# diff_probe_top.net
KiCad netlist of a schematic drawn in Altium Designer
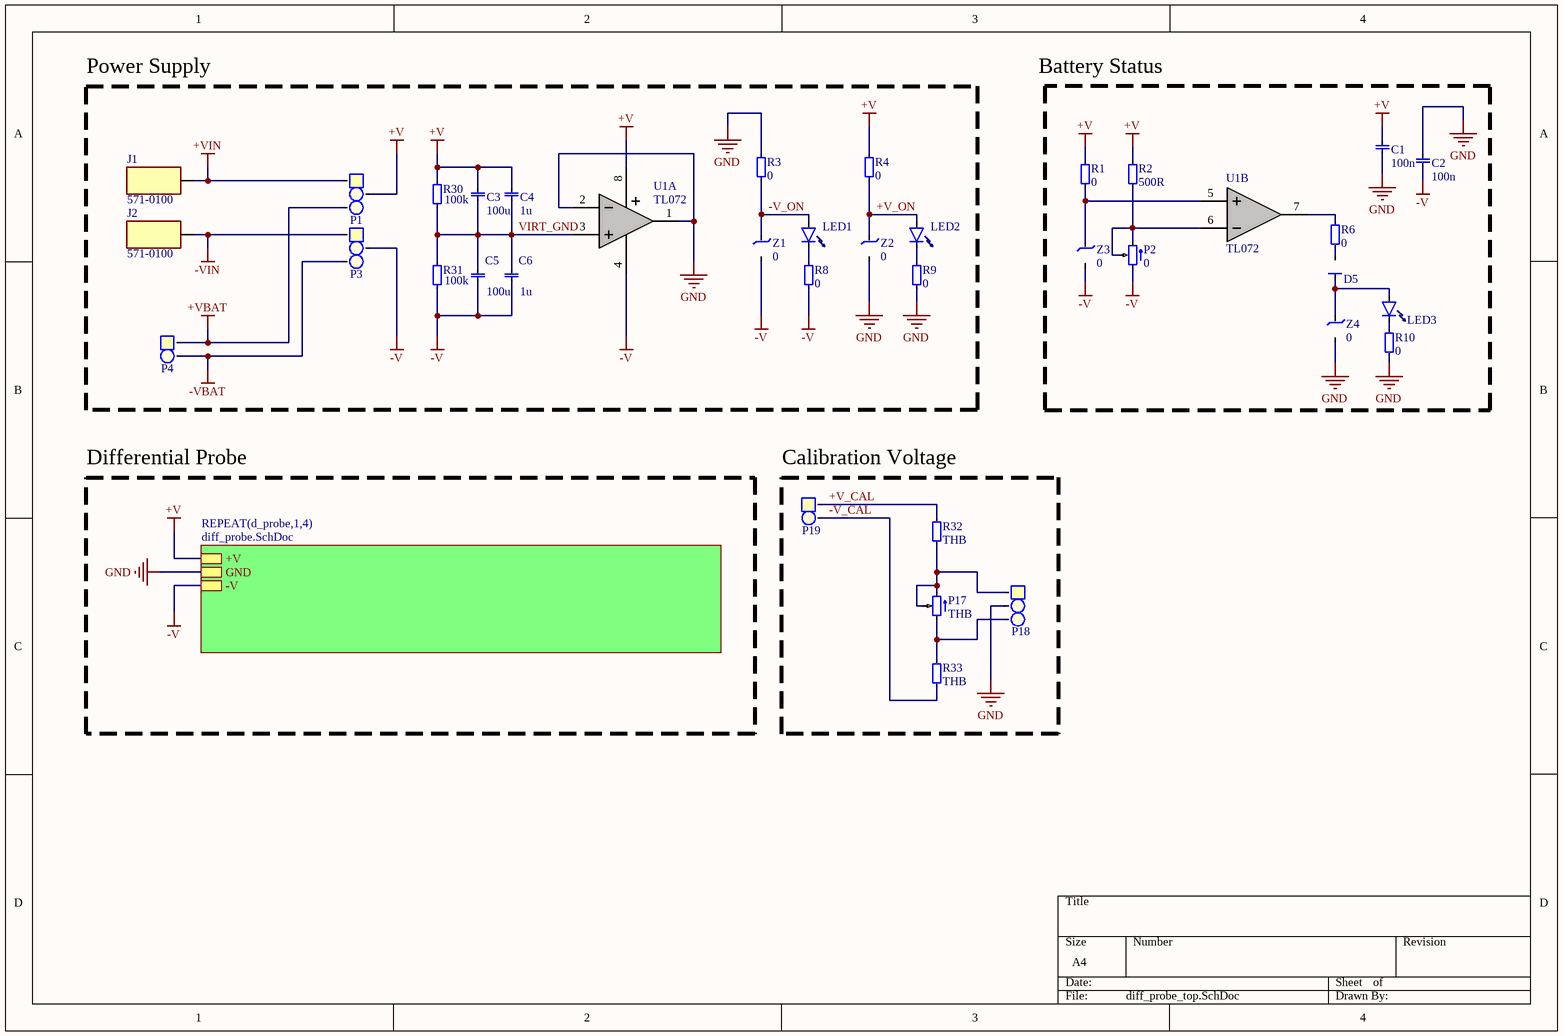
[diagram p0: diff_probe_top.SchDoc]

(export (version "E")
  (design (tool "Eeschema 10.0.6"))
  (components
    (comp (ref "C1")
      (value "100n")
      (footprint "0603 cap")
      (fields (field (name "Comment") "0603, capacitor"))
      (libsource (lib "jclib") (part "0603, capacitor"))
    )
    (comp (ref "C2")
      (value "100n")
      (footprint "0603 cap")
      (fields (field (name "Comment") "0603, capacitor"))
      (libsource (lib "jclib") (part "0603, capacitor"))
    )
    (comp (ref "C3")
      (value "100u")
      (footprint "1206, capasitor")
      (fields (field (name "Comment") "1206, capacitor"))
      (libsource (lib "jclib") (part "1206, capacitor"))
    )
    (comp (ref "C4")
      (value "1u")
      (footprint "1206, capasitor")
      (fields (field (name "Comment") "1206, capacitor"))
      (libsource (lib "jclib") (part "1206, capacitor"))
    )
    (comp (ref "C5")
      (value "100u")
      (footprint "1206, capasitor")
      (fields (field (name "Comment") "1206, capacitor"))
      (libsource (lib "jclib") (part "1206, capacitor"))
    )
    (comp (ref "C6")
      (value "1u")
      (footprint "1206, capasitor")
      (fields (field (name "Comment") "1206, capacitor"))
      (libsource (lib "jclib") (part "1206, capacitor"))
    )
    (comp (ref "D5") (value "Diode, SMD") (footprint "SOD323") (libsource (lib "jclib") (part "Diode, SMD")))
    (comp (ref "J1")
      (value "571-0100")
      (footprint "Banana Conn VCC")
      (description "Banana Connector 571-0100")
      (fields (field (name "MOUSER PART NUMBER") "164-6218"))
      (libsource (lib "jclib") (part "Banana conn"))
    )
    (comp (ref "J2")
      (value "571-0100")
      (footprint "Banana Conn GND")
      (description "Banana Connector 571-0100")
      (fields (field (name "MOUSER PART NUMBER") "164-6218"))
      (libsource (lib "jclib") (part "Banana conn"))
    )
    (comp (ref "LED1")
      (value "0805, LED")
      (footprint "0805_led")
      (libsource (lib "jclib") (part "0805, LED"))
    )
    (comp (ref "LED2")
      (value "0805, LED")
      (footprint "0805_led")
      (libsource (lib "jclib") (part "0805, LED"))
    )
    (comp (ref "LED3")
      (value "0805, LED")
      (footprint "0805_led")
      (libsource (lib "jclib") (part "0805, LED"))
    )
    (comp (ref "P1")
      (value "1x3 Pin Header Mux")
      (footprint "padThree_L")
      (description "2.54 mm")
      (libsource (lib "jclib") (part "1x3 Pin Header Mux"))
    )
    (comp (ref "P2")
      (value "0")
      (footprint "PV36W104C01B00")
      (fields (field (name "Comment") "Pot"))
      (libsource (lib "jclib") (part "Pot"))
    )
    (comp (ref "P3")
      (value "1x3 Pin Header Mux")
      (footprint "padThree_L")
      (description "2.54 mm")
      (libsource (lib "jclib") (part "1x3 Pin Header Mux"))
    )
    (comp (ref "P4")
      (value "1x2 Pin Header")
      (footprint "padtwo_L")
      (description "2.54 mm, TH")
      (libsource (lib "jclib") (part "1x2 Pin Header"))
    )
    (comp (ref "P17")
      (value "THB")
      (footprint "PV36W104C01B00")
      (fields (field (name "Comment") "Pot"))
      (libsource (lib "jclib") (part "Pot"))
    )
    (comp (ref "P18")
      (value "1x3 Pin Header")
      (footprint "1x3_horizontal")
      (description "2.54 mm")
      (libsource (lib "jclib") (part "1x3 Pin Header"))
    )
    (comp (ref "P19")
      (value "1x2 Pin Header")
      (footprint "1x2 Bent")
      (description "2.54 mm, TH")
      (libsource (lib "jclib") (part "1x2 Pin Header"))
    )
    (comp (ref "R1")
      (value "0")
      (footprint "0603")
      (fields (field (name "Comment") "0603, resistor"))
      (libsource (lib "jclib") (part "0603, resistor"))
    )
    (comp (ref "R2")
      (value "500R")
      (footprint "0603")
      (fields (field (name "Comment") "0603, resistor"))
      (libsource (lib "jclib") (part "0603, resistor"))
    )
    (comp (ref "R3")
      (value "0")
      (footprint "0603")
      (fields (field (name "Comment") "0603, resistor"))
      (libsource (lib "jclib") (part "0603, resistor"))
    )
    (comp (ref "R4")
      (value "0")
      (footprint "0603")
      (fields (field (name "Comment") "0603, resistor"))
      (libsource (lib "jclib") (part "0603, resistor"))
    )
    (comp (ref "R6")
      (value "0")
      (footprint "0603")
      (fields (field (name "Comment") "0603, resistor"))
      (libsource (lib "jclib") (part "0603, resistor"))
    )
    (comp (ref "R8")
      (value "0")
      (footprint "0603")
      (fields (field (name "Comment") "0603, resistor"))
      (libsource (lib "jclib") (part "0603, resistor"))
    )
    (comp (ref "R9")
      (value "0")
      (footprint "0603")
      (fields (field (name "Comment") "0603, resistor"))
      (libsource (lib "jclib") (part "0603, resistor"))
    )
    (comp (ref "R10")
      (value "0")
      (footprint "0603")
      (fields (field (name "Comment") "0603, resistor"))
      (libsource (lib "jclib") (part "0603, resistor"))
    )
    (comp (ref "R30")
      (value "100k")
      (footprint "0603")
      (fields (field (name "Comment") "0603, resistor"))
      (libsource (lib "jclib") (part "0603, resistor"))
    )
    (comp (ref "R31")
      (value "100k")
      (footprint "0603")
      (fields (field (name "Comment") "0603, resistor"))
      (libsource (lib "jclib") (part "0603, resistor"))
    )
    (comp (ref "R32")
      (value "THB")
      (footprint "0603")
      (fields (field (name "Comment") "0603, resistor"))
      (libsource (lib "jclib") (part "0603, resistor"))
    )
    (comp (ref "R33")
      (value "THB")
      (footprint "0603")
      (fields (field (name "Comment") "0603, resistor"))
      (libsource (lib "jclib") (part "0603, resistor"))
    )
    (comp (ref "U1")
      (value "TL072")
      (footprint "SOIC8")
      (description "Dual FET-Input Operational Amplifier")
      (libsource (lib "jclib") (part "TL072"))
    )
    (comp (ref "Z1")
      (value "0")
      (footprint "DO-214AA")
      (fields (field (name "Comment") "Zener Diode"))
      (libsource (lib "jclib") (part "Zener Diode"))
    )
    (comp (ref "Z2")
      (value "0")
      (footprint "DO-214AA")
      (fields (field (name "Comment") "Zener Diode"))
      (libsource (lib "jclib") (part "Zener Diode"))
    )
    (comp (ref "Z3")
      (value "0")
      (footprint "DO-214AA")
      (fields (field (name "Comment") "Zener Diode"))
      (libsource (lib "jclib") (part "Zener Diode"))
    )
    (comp (ref "Z4")
      (value "0")
      (footprint "DO-214AA")
      (fields (field (name "Comment") "Zener Diode"))
      (libsource (lib "jclib") (part "Zener Diode"))
    )
  )
  (nets
    (net (code "1") (name "+V") (class "Default")
      (node (ref "C1") (pin "1") (pinfunction "1_1") (pintype "passive"))
      (node (ref "C3") (pin "1") (pinfunction "1_1") (pintype "passive"))
      (node (ref "C4") (pin "1") (pinfunction "1_1") (pintype "passive"))
      (node (ref "P1") (pin "2") (pinfunction "2_2") (pintype "passive"))
      (node (ref "R1") (pin "0") (pinfunction "0_0") (pintype "passive"))
      (node (ref "R2") (pin "1") (pinfunction "1_1") (pintype "passive"))
      (node (ref "R30") (pin "0") (pinfunction "0_0") (pintype "passive"))
      (node (ref "R4") (pin "0") (pinfunction "0_0") (pintype "passive"))
      (node (ref "U1") (pin "8") (pinfunction "V+_8") (pintype "power_in"))
    )
    (net (code "2") (name "+VBAT") (class "Default")
      (node (ref "P1") (pin "3") (pinfunction "3_3") (pintype "passive"))
      (node (ref "P4") (pin "1") (pinfunction "1_1") (pintype "passive"))
    )
    (net (code "3") (name "+VIN") (class "Default")
      (node (ref "J1") (pin "1") (pinfunction "1_1") (pintype "passive"))
      (node (ref "P1") (pin "1") (pinfunction "1_1") (pintype "passive"))
    )
    (net (code "4") (name "-V") (class "Default")
      (node (ref "C2") (pin "1") (pinfunction "1_1") (pintype "passive"))
      (node (ref "C5") (pin "0") (pinfunction "0_0") (pintype "passive"))
      (node (ref "C6") (pin "0") (pinfunction "0_0") (pintype "passive"))
      (node (ref "P2") (pin "1") (pinfunction "1_1") (pintype "passive"))
      (node (ref "P3") (pin "2") (pinfunction "2_2") (pintype "passive"))
      (node (ref "R31") (pin "1") (pinfunction "1_1") (pintype "passive"))
      (node (ref "R8") (pin "1") (pinfunction "1_1") (pintype "passive"))
      (node (ref "U1") (pin "4") (pinfunction "V-_4") (pintype "power_in"))
      (node (ref "Z1") (pin "1") (pinfunction "Anode_1") (pintype "passive"))
      (node (ref "Z3") (pin "1") (pinfunction "Anode_1") (pintype "passive"))
    )
    (net (code "5") (name "-VBAT") (class "Default")
      (node (ref "P3") (pin "3") (pinfunction "3_3") (pintype "passive"))
      (node (ref "P4") (pin "2") (pinfunction "2_2") (pintype "passive"))
    )
    (net (code "6") (name "-VIN") (class "Default")
      (node (ref "J2") (pin "1") (pinfunction "1_1") (pintype "passive"))
      (node (ref "P3") (pin "1") (pinfunction "1_1") (pintype "passive"))
    )
    (net (code "7") (name "/+V_CAL") (class "Default")
      (node (ref "P19") (pin "1") (pinfunction "1_1") (pintype "passive"))
      (node (ref "R32") (pin "0") (pinfunction "0_0") (pintype "passive"))
    )
    (net (code "8") (name "/+V_ON") (class "Default")
      (node (ref "LED2") (pin "1") (pinfunction "1_1") (pintype "passive"))
      (node (ref "R4") (pin "1") (pinfunction "1_1") (pintype "passive"))
      (node (ref "Z2") (pin "2") (pinfunction "Cathode_2") (pintype "passive"))
    )
    (net (code "9") (name "/-V_CAL") (class "Default")
      (node (ref "P19") (pin "2") (pinfunction "2_2") (pintype "passive"))
      (node (ref "R33") (pin "1") (pinfunction "1_1") (pintype "passive"))
    )
    (net (code "10") (name "/-V_ON") (class "Default")
      (node (ref "LED1") (pin "1") (pinfunction "1_1") (pintype "passive"))
      (node (ref "R3") (pin "1") (pinfunction "1_1") (pintype "passive"))
      (node (ref "Z1") (pin "2") (pinfunction "Cathode_2") (pintype "passive"))
    )
    (net (code "11") (name "/VIRT_GND") (class "Default")
      (node (ref "C3") (pin "0") (pinfunction "0_0") (pintype "passive"))
      (node (ref "C4") (pin "0") (pinfunction "0_0") (pintype "passive"))
      (node (ref "C5") (pin "1") (pinfunction "1_1") (pintype "passive"))
      (node (ref "C6") (pin "1") (pinfunction "1_1") (pintype "passive"))
      (node (ref "R30") (pin "1") (pinfunction "1_1") (pintype "passive"))
      (node (ref "R31") (pin "0") (pinfunction "0_0") (pintype "passive"))
      (node (ref "U1") (pin "3") (pinfunction "IN+_3") (pintype "passive"))
    )
    (net (code "12") (name "GND") (class "Default")
      (node (ref "C1") (pin "0") (pinfunction "0_0") (pintype "passive"))
      (node (ref "C2") (pin "0") (pinfunction "0_0") (pintype "passive"))
      (node (ref "P18") (pin "2") (pinfunction "2_2") (pintype "passive"))
      (node (ref "R10") (pin "1") (pinfunction "1_1") (pintype "passive"))
      (node (ref "R3") (pin "0") (pinfunction "0_0") (pintype "passive"))
      (node (ref "R9") (pin "1") (pinfunction "1_1") (pintype "passive"))
      (node (ref "U1") (pin "1") (pinfunction "OUT1_1") (pintype "passive"))
      (node (ref "U1") (pin "2") (pinfunction "IN-_2") (pintype "passive"))
      (node (ref "Z2") (pin "1") (pinfunction "Anode_1") (pintype "passive"))
      (node (ref "Z4") (pin "1") (pinfunction "Anode_1") (pintype "passive"))
    )
    (net (code "13") (name "Net-(D5-Pad2)") (class "Default")
      (node (ref "D5") (pin "2") (pinfunction "2_2") (pintype "passive"))
      (node (ref "R6") (pin "1") (pinfunction "1_1") (pintype "passive"))
    )
    (net (code "14") (name "Net-(LED1-Cathode)") (class "Default")
      (node (ref "LED1") (pin "0") (pinfunction "Cathode_0") (pintype "passive"))
      (node (ref "R8") (pin "0") (pinfunction "0_0") (pintype "passive"))
    )
    (net (code "15") (name "Net-(LED2-Cathode)") (class "Default")
      (node (ref "LED2") (pin "0") (pinfunction "Cathode_0") (pintype "passive"))
      (node (ref "R9") (pin "0") (pinfunction "0_0") (pintype "passive"))
    )
    (net (code "16") (name "Net-(LED3-Cathode)") (class "Default")
      (node (ref "LED3") (pin "0") (pinfunction "Cathode_0") (pintype "passive"))
      (node (ref "R10") (pin "0") (pinfunction "0_0") (pintype "passive"))
    )
    (net (code "17") (name "Net-(P17-Pad1)") (class "Default")
      (node (ref "P17") (pin "1") (pinfunction "1_1") (pintype "passive"))
      (node (ref "P18") (pin "3") (pinfunction "3_3") (pintype "passive"))
      (node (ref "R33") (pin "0") (pinfunction "0_0") (pintype "passive"))
    )
    (net (code "18") (name "Net-(P17-Pad2)") (class "Default")
      (node (ref "P17") (pin "2") (pinfunction "2_2") (pintype "passive"))
      (node (ref "P17") (pin "3") (pinfunction "3_3") (pintype "passive"))
      (node (ref "P18") (pin "1") (pinfunction "1_1") (pintype "passive"))
      (node (ref "R32") (pin "1") (pinfunction "1_1") (pintype "passive"))
    )
    (net (code "19") (name "Net-(U1B-IN+)") (class "Default")
      (node (ref "R1") (pin "1") (pinfunction "1_1") (pintype "passive"))
      (node (ref "U1") (pin "5") (pinfunction "IN+_5") (pintype "passive"))
      (node (ref "Z3") (pin "2") (pinfunction "Cathode_2") (pintype "passive"))
    )
    (net (code "20") (name "Net-(U1B-IN-)") (class "Default")
      (node (ref "P2") (pin "2") (pinfunction "2_2") (pintype "passive"))
      (node (ref "P2") (pin "3") (pinfunction "3_3") (pintype "passive"))
      (node (ref "R2") (pin "0") (pinfunction "0_0") (pintype "passive"))
      (node (ref "U1") (pin "6") (pinfunction "IN-_6") (pintype "passive"))
    )
    (net (code "21") (name "Net-(U1B-OUT2)") (class "Default")
      (node (ref "R6") (pin "0") (pinfunction "0_0") (pintype "passive"))
      (node (ref "U1") (pin "7") (pinfunction "OUT2_7") (pintype "passive"))
    )
    (net (code "22") (name "Net-(Z4-Cathode)") (class "Default")
      (node (ref "D5") (pin "1") (pinfunction "1_1") (pintype "passive"))
      (node (ref "LED3") (pin "1") (pinfunction "1_1") (pintype "passive"))
      (node (ref "Z4") (pin "2") (pinfunction "Cathode_2") (pintype "passive"))
    )
  )
)
